# ESP_BLE.net
KiCad netlist of a schematic drawn in Altium Designer
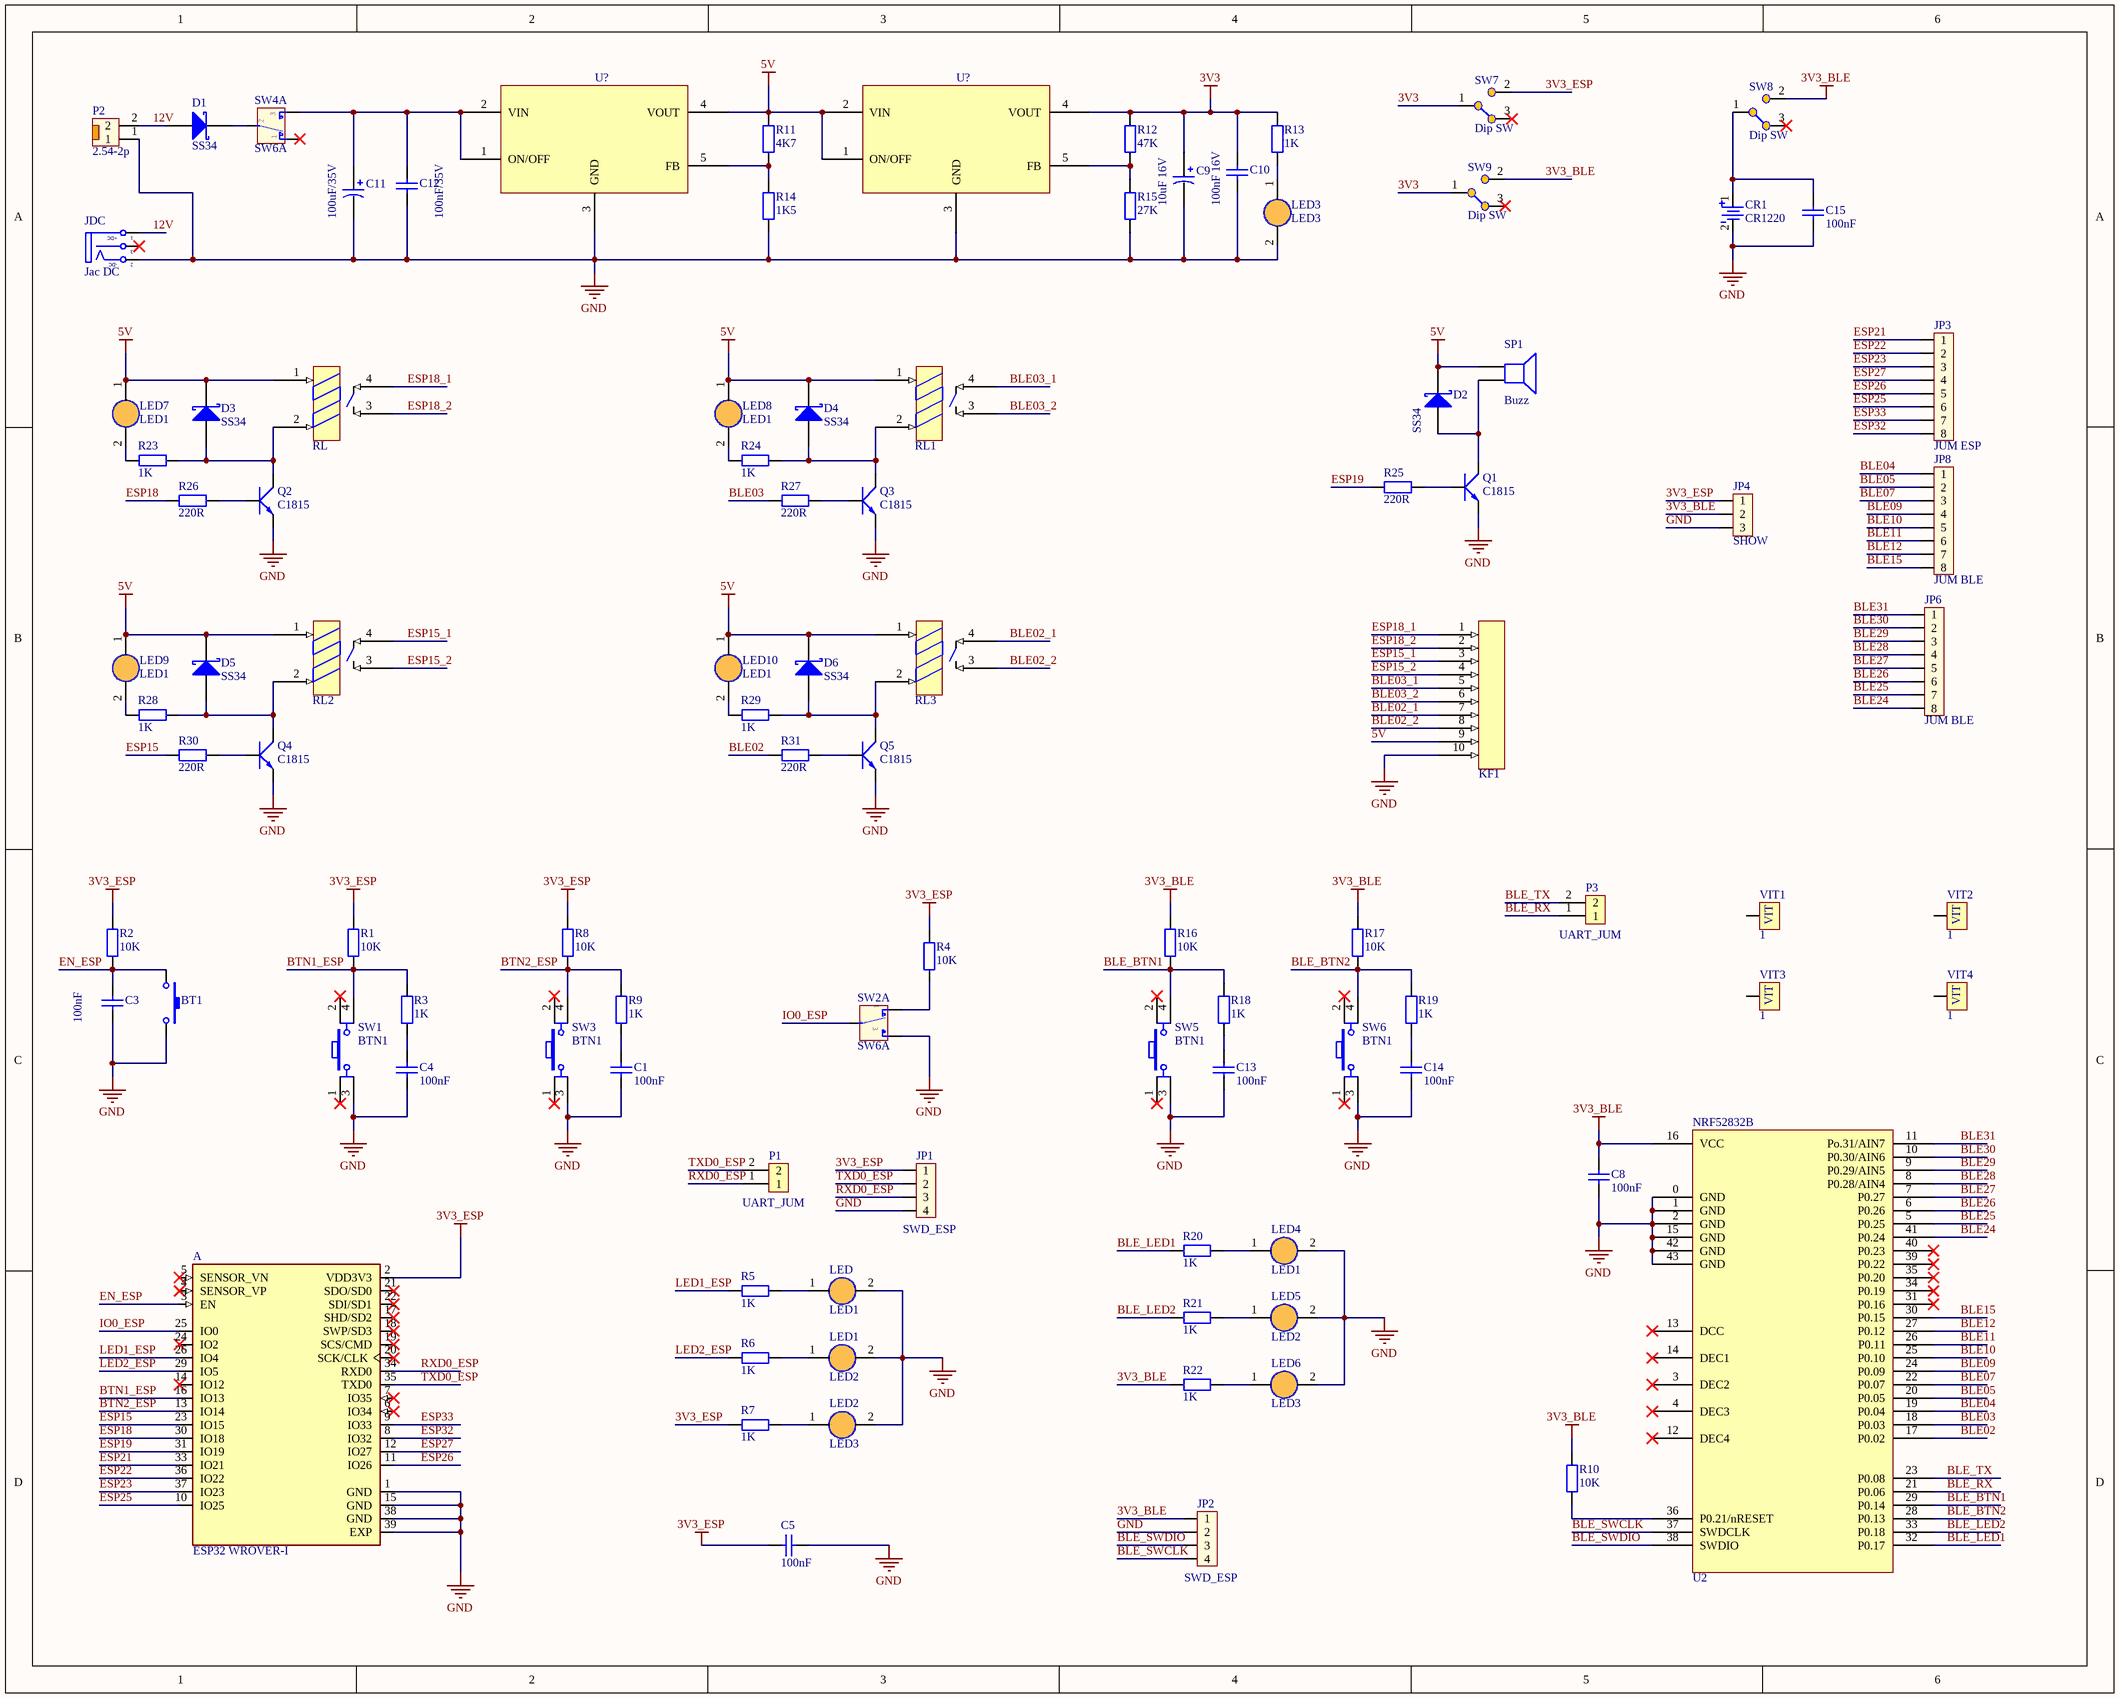
[diagram p0: ESP_BLE.SchDoc]

(export (version "E")
  (design (tool "Eeschema 10.0.6"))
  (components
    (comp (ref "A")
      (value "ESP32 WROVER-I")
      (footprint "ESP32-WROVER-I")
      (fields (field (name "MP") "ESP32-WROVER-I") (field (name "MF") "Espressif Systems"))
      (libsource (lib "Altium_Lib_by_KhueNguyenCreator") (part "ESP32 WROVER-I"))
    )
    (comp (ref "BT1")
      (value "Nút Nhấn 2 Chân 3x6x2.5MM SMD")
      (footprint "Nut Nhan 2 Chan SMD_N")
      (description "Dán")
      (libsource (lib "NhomLib") (part "Nut Nhan 2 Chan SMD"))
    )
    (comp (ref "C1")
      (value "100nF")
      (footprint "tu 0805")
      (description "Dán")
      (libsource (lib "NhomLib") (part "Tu 0805 33nF 50V 20%"))
    )
    (comp (ref "C3")
      (value "100nF")
      (footprint "tu 0805")
      (description "Dán")
      (libsource (lib "NhomLib") (part "Tu 0805 33nF 50V 20%"))
    )
    (comp (ref "C4")
      (value "100nF")
      (footprint "tu 0805")
      (description "Dán")
      (libsource (lib "NhomLib") (part "Tu 0805 33nF 50V 20%"))
    )
    (comp (ref "C5")
      (value "100nF")
      (footprint "tu 0805")
      (description "Dán")
      (libsource (lib "NhomLib") (part "Tu 0805 33nF 50V 20%"))
    )
    (comp (ref "C8")
      (value "100nF")
      (footprint "tu 0805")
      (description "Dán")
      (libsource (lib "NhomLib") (part "Tu 0805 33nF 50V 20%"))
    )
    (comp (ref "C9")
      (value "10uF 16V")
      (footprint "CAP_ALUM_SMD_5054_TYPE_C")
      (description "CAP ALUM 33uF 20% 16V SMD")
      (fields (field (name "MPN") "EEE-FK1C330P") (field (name "MFR") "Panasonic"))
      (libsource (lib "NhomLib") (part "EEE-FK1C330P"))
    )
    (comp (ref "C10")
      (value "100nF 16V")
      (footprint "tu 0805")
      (description "Dán")
      (libsource (lib "NhomLib") (part "Tu 0805 33nF 50V 20%"))
    )
    (comp (ref "C11")
      (value "100uF/35V")
      (footprint "CAP_ALUM_SMD_100102_TYPE_G")
      (description "CAP ALUM 330uF 20% 35V SMD")
      (fields (field (name "MPN") "EEE-FK1C331P") (field (name "MFR") "Panasonic"))
      (libsource (lib "NhomLib") (part "EEE-FK1C331P"))
    )
    (comp (ref "C12")
      (value "100nF/35V")
      (footprint "tu 0805")
      (description "Dán")
      (libsource (lib "NhomLib") (part "Tu 0805 33nF 50V 20%"))
    )
    (comp (ref "C13")
      (value "100nF")
      (footprint "tu 0805")
      (description "Dán")
      (libsource (lib "NhomLib") (part "Tu 0805 33nF 50V 20%"))
    )
    (comp (ref "C14")
      (value "100nF")
      (footprint "tu 0805")
      (description "Dán")
      (libsource (lib "NhomLib") (part "Tu 0805 33nF 50V 20%"))
    )
    (comp (ref "C15")
      (value "100nF")
      (footprint "tu 0805")
      (description "Dán")
      (libsource (lib "NhomLib") (part "Tu 0805 33nF 50V 20%"))
    )
    (comp (ref "CR1")
      (value "CR1220")
      (footprint "CR1220_HOLDER_SMD")
      (libsource (lib "VINH TRI") (part "CR1220"))
    )
    (comp (ref "D1")
      (value "SS34")
      (footprint "DIODE_DO214AC_SMA")
      (description "DIODE SCHOTTKY 40V 3A SMA")
      (libsource (lib "NhomLib") (part "SS34"))
    )
    (comp (ref "D2")
      (value "SS34")
      (footprint "DIODE_DO214AC_SMA")
      (description "DIODE SCHOTTKY 40V 3A SMA")
      (libsource (lib "NhomLib") (part "SS34"))
    )
    (comp (ref "D3")
      (value "SS34")
      (footprint "DIODE_DO214AC_SMA")
      (description "DIODE SCHOTTKY 40V 3A SMA")
      (libsource (lib "NhomLib") (part "SS34"))
    )
    (comp (ref "D4")
      (value "SS34")
      (footprint "DIODE_DO214AC_SMA")
      (description "DIODE SCHOTTKY 40V 3A SMA")
      (libsource (lib "NhomLib") (part "SS34"))
    )
    (comp (ref "D5")
      (value "SS34")
      (footprint "DIODE_DO214AC_SMA")
      (description "DIODE SCHOTTKY 40V 3A SMA")
      (libsource (lib "NhomLib") (part "SS34"))
    )
    (comp (ref "D6")
      (value "SS34")
      (footprint "DIODE_DO214AC_SMA")
      (description "DIODE SCHOTTKY 40V 3A SMA")
      (libsource (lib "NhomLib") (part "SS34"))
    )
    (comp (ref "JDC")
      (value "Jac DC")
      (footprint "DC-IN")
      (description "Jac DC input")
      (libsource (lib "NhomLib") (part "DCIN"))
    )
    (comp (ref "JP1")
      (value "SWD_ESP")
      (footprint "JUMP DON DUC 2.54_4P")
      (description "Cắm")
      (libsource (lib "SCH Chuan") (part "Jump Don Duc 2.54_4P"))
    )
    (comp (ref "JP2")
      (value "SWD_ESP")
      (footprint "JUMP DON DUC 2.54_4P")
      (description "Cắm")
      (libsource (lib "SCH Chuan") (part "Jump Don Duc 2.54_4P"))
    )
    (comp (ref "JP3")
      (value "JUM ESP")
      (footprint "Jump Don Duc Thang 2.54_8p")
      (description "Cắm")
      (libsource (lib "NhomLib") (part "Jump Don Duc 2.54_8P"))
    )
    (comp (ref "JP4")
      (value "SHOW")
      (footprint "jump don duc thang 2.54_3p")
      (description "Cắm")
      (libsource (lib "NhomLib") (part "Jump Don Duc 2.54_3P"))
    )
    (comp (ref "JP6")
      (value "JUM BLE")
      (footprint "Jump Don Duc Thang 2.54_8p")
      (description "Cắm")
      (libsource (lib "NhomLib") (part "Jump Don Duc 2.54_8P"))
    )
    (comp (ref "JP8")
      (value "JUM BLE")
      (footprint "Jump Don Duc Thang 2.54_8p")
      (description "Cắm")
      (libsource (lib "NhomLib") (part "Jump Don Duc 2.54_8P"))
    )
    (comp (ref "KF1")
      (value "KF142R-10")
      (footprint "KF10")
      (description "KF142R-10P-5.08mm")
      (libsource (lib "B212H_01") (part "KF10"))
    )
    (comp (ref "LED")
      (value "LED1")
      (footprint "led 0805")
      (description "Dán")
      (libsource (lib "NhomLib") (part "Led 0805 Xanh Duong"))
    )
    (comp (ref "LED1")
      (value "LED2")
      (footprint "led 0805")
      (description "Dán")
      (libsource (lib "NhomLib") (part "Led 0805 Xanh Duong"))
    )
    (comp (ref "LED2")
      (value "LED3")
      (footprint "led 0805")
      (description "Dán")
      (libsource (lib "NhomLib") (part "Led 0805 Xanh Duong"))
    )
    (comp (ref "LED3")
      (value "LED3")
      (footprint "led 0805")
      (description "Dán")
      (libsource (lib "NhomLib") (part "Led 0805 Xanh Duong"))
    )
    (comp (ref "LED4")
      (value "LED1")
      (footprint "led 0805")
      (description "Dán")
      (libsource (lib "NhomLib") (part "Led 0805 Xanh Duong"))
    )
    (comp (ref "LED5")
      (value "LED2")
      (footprint "led 0805")
      (description "Dán")
      (libsource (lib "NhomLib") (part "Led 0805 Xanh Duong"))
    )
    (comp (ref "LED6")
      (value "LED3")
      (footprint "led 0805")
      (description "Dán")
      (libsource (lib "NhomLib") (part "Led 0805 Xanh Duong"))
    )
    (comp (ref "LED7")
      (value "LED1")
      (footprint "led 0805")
      (description "Dán")
      (libsource (lib "NhomLib") (part "Led 0805 Xanh Duong"))
    )
    (comp (ref "LED8")
      (value "LED1")
      (footprint "led 0805")
      (description "Dán")
      (libsource (lib "NhomLib") (part "Led 0805 Xanh Duong"))
    )
    (comp (ref "LED9")
      (value "LED1")
      (footprint "led 0805")
      (description "Dán")
      (libsource (lib "NhomLib") (part "Led 0805 Xanh Duong"))
    )
    (comp (ref "LED10")
      (value "LED1")
      (footprint "led 0805")
      (description "Dán")
      (libsource (lib "NhomLib") (part "Led 0805 Xanh Duong"))
    )
    (comp (ref "MIC1")
      (value "U?")
      (footprint "Mic5V")
      (description "3A")
      (libsource (lib "node_mcu") (part "Mic5V"))
    )
    (comp (ref "MIC2")
      (value "U?")
      (footprint "Mic5V")
      (description "3A")
      (libsource (lib "node_mcu") (part "Mic5V"))
    )
    (comp (ref "NRF52832") (value "U2") (footprint "NRF52832") (libsource (lib "NRF52832") (part "U?")))
    (comp (ref "P1")
      (value "UART_JUM")
      (footprint "Jump don duc 2.54_2P")
      (description "Cắm")
      (libsource (lib "NhomLib") (part "jump don duc 2.54_2p"))
    )
    (comp (ref "P2")
      (value "2.54-2p")
      (footprint "Header Duc Thang 2P 2.54")
      (description "Cắm")
      (libsource (lib "NhomLib") (part "Header 2.54-2p Duc Thang"))
    )
    (comp (ref "P3")
      (value "UART_JUM")
      (footprint "Jump don duc 2.54_2P")
      (description "Cắm")
      (libsource (lib "NhomLib") (part "jump don duc 2.54_2p"))
    )
    (comp (ref "Q1")
      (value "C1815")
      (footprint "SOT23B")
      (description "NPN 600mW, ECB")
      (libsource (lib "syhaunguyen") (part "C1815"))
    )
    (comp (ref "Q2")
      (value "C1815")
      (footprint "SOT23B")
      (description "NPN 600mW, ECB")
      (libsource (lib "syhaunguyen") (part "C1815"))
    )
    (comp (ref "Q3")
      (value "C1815")
      (footprint "SOT23B")
      (description "NPN 600mW, ECB")
      (libsource (lib "syhaunguyen") (part "C1815"))
    )
    (comp (ref "Q4")
      (value "C1815")
      (footprint "SOT23B")
      (description "NPN 600mW, ECB")
      (libsource (lib "syhaunguyen") (part "C1815"))
    )
    (comp (ref "Q5")
      (value "C1815")
      (footprint "SOT23B")
      (description "NPN 600mW, ECB")
      (libsource (lib "syhaunguyen") (part "C1815"))
    )
    (comp (ref "R1")
      (value "10K")
      (footprint "tro 0805")
      (description "Dán")
      (libsource (lib "NhomLib") (part "Tro 0805 1% 0.33R"))
    )
    (comp (ref "R2")
      (value "10K")
      (footprint "tro 0805")
      (description "Dán")
      (libsource (lib "NhomLib") (part "Tro 0805 1% 0.33R"))
    )
    (comp (ref "R3")
      (value "1K")
      (footprint "tro 0805")
      (description "Dán")
      (libsource (lib "NhomLib") (part "Tro 0805 1% 0.33R"))
    )
    (comp (ref "R4")
      (value "10K")
      (footprint "tro 0805")
      (description "Dán")
      (libsource (lib "NhomLib") (part "Tro 0805 1% 0.33R"))
    )
    (comp (ref "R5")
      (value "1K")
      (footprint "tro 0805")
      (description "Dán")
      (libsource (lib "NhomLib") (part "Tro 0805 1% 0.33R"))
    )
    (comp (ref "R6")
      (value "1K")
      (footprint "tro 0805")
      (description "Dán")
      (libsource (lib "NhomLib") (part "Tro 0805 1% 0.33R"))
    )
    (comp (ref "R7")
      (value "1K")
      (footprint "tro 0805")
      (description "Dán")
      (libsource (lib "NhomLib") (part "Tro 0805 1% 0.33R"))
    )
    (comp (ref "R8")
      (value "10K")
      (footprint "tro 0805")
      (description "Dán")
      (libsource (lib "NhomLib") (part "Tro 0805 1% 0.33R"))
    )
    (comp (ref "R9")
      (value "1K")
      (footprint "tro 0805")
      (description "Dán")
      (libsource (lib "NhomLib") (part "Tro 0805 1% 0.33R"))
    )
    (comp (ref "R10")
      (value "10K")
      (footprint "tro 0805")
      (description "Dán")
      (libsource (lib "NhomLib") (part "Tro 0805 1% 0.33R"))
    )
    (comp (ref "R11")
      (value "4K7")
      (footprint "tro 0805")
      (description "Dán")
      (libsource (lib "NhomLib") (part "Tro 0805 1% 0.33R"))
    )
    (comp (ref "R12")
      (value "47K")
      (footprint "tro 0805")
      (description "Dán")
      (libsource (lib "NhomLib") (part "Tro 0805 1% 0.33R"))
    )
    (comp (ref "R13")
      (value "1K")
      (footprint "tro 0805")
      (description "Dán")
      (libsource (lib "NhomLib") (part "Tro 0805 1% 0.33R"))
    )
    (comp (ref "R14")
      (value "1K5")
      (footprint "tro 0805")
      (description "Dán")
      (libsource (lib "NhomLib") (part "Tro 0805 1% 0.33R"))
    )
    (comp (ref "R15")
      (value "27K")
      (footprint "tro 0805")
      (description "Dán")
      (libsource (lib "NhomLib") (part "Tro 0805 1% 0.33R"))
    )
    (comp (ref "R16")
      (value "10K")
      (footprint "tro 0805")
      (description "Dán")
      (libsource (lib "NhomLib") (part "Tro 0805 1% 0.33R"))
    )
    (comp (ref "R17")
      (value "10K")
      (footprint "tro 0805")
      (description "Dán")
      (libsource (lib "NhomLib") (part "Tro 0805 1% 0.33R"))
    )
    (comp (ref "R18")
      (value "1K")
      (footprint "tro 0805")
      (description "Dán")
      (libsource (lib "NhomLib") (part "Tro 0805 1% 0.33R"))
    )
    (comp (ref "R19")
      (value "1K")
      (footprint "tro 0805")
      (description "Dán")
      (libsource (lib "NhomLib") (part "Tro 0805 1% 0.33R"))
    )
    (comp (ref "R20")
      (value "1K")
      (footprint "tro 0805")
      (description "Dán")
      (libsource (lib "NhomLib") (part "Tro 0805 1% 0.33R"))
    )
    (comp (ref "R21")
      (value "1K")
      (footprint "tro 0805")
      (description "Dán")
      (libsource (lib "NhomLib") (part "Tro 0805 1% 0.33R"))
    )
    (comp (ref "R22")
      (value "1K")
      (footprint "tro 0805")
      (description "Dán")
      (libsource (lib "NhomLib") (part "Tro 0805 1% 0.33R"))
    )
    (comp (ref "R23")
      (value "1K")
      (footprint "tro 0805")
      (description "Dán")
      (libsource (lib "NhomLib") (part "Tro 0805 1% 0.33R"))
    )
    (comp (ref "R24")
      (value "1K")
      (footprint "tro 0805")
      (description "Dán")
      (libsource (lib "NhomLib") (part "Tro 0805 1% 0.33R"))
    )
    (comp (ref "R25")
      (value "220R")
      (footprint "tro 0805")
      (description "Dán")
      (libsource (lib "NhomLib") (part "Tro 0805 1% 0.33R"))
    )
    (comp (ref "R26")
      (value "220R")
      (footprint "tro 0805")
      (description "Dán")
      (libsource (lib "NhomLib") (part "Tro 0805 1% 0.33R"))
    )
    (comp (ref "R27")
      (value "220R")
      (footprint "tro 0805")
      (description "Dán")
      (libsource (lib "NhomLib") (part "Tro 0805 1% 0.33R"))
    )
    (comp (ref "R28")
      (value "1K")
      (footprint "tro 0805")
      (description "Dán")
      (libsource (lib "NhomLib") (part "Tro 0805 1% 0.33R"))
    )
    (comp (ref "R29")
      (value "1K")
      (footprint "tro 0805")
      (description "Dán")
      (libsource (lib "NhomLib") (part "Tro 0805 1% 0.33R"))
    )
    (comp (ref "R30")
      (value "220R")
      (footprint "tro 0805")
      (description "Dán")
      (libsource (lib "NhomLib") (part "Tro 0805 1% 0.33R"))
    )
    (comp (ref "R31")
      (value "220R")
      (footprint "tro 0805")
      (description "Dán")
      (libsource (lib "NhomLib") (part "Tro 0805 1% 0.33R"))
    )
    (comp (ref "RL") (value "Relay-4") (footprint "Relay-4") (libsource (lib "B212H_01") (part "Relay-4")))
    (comp (ref "RL1") (value "Relay-4") (footprint "Relay-4") (libsource (lib "B212H_01") (part "Relay-4")))
    (comp (ref "RL2") (value "Relay-4") (footprint "Relay-4") (libsource (lib "B212H_01") (part "Relay-4")))
    (comp (ref "RL3") (value "Relay-4") (footprint "Relay-4") (libsource (lib "B212H_01") (part "Relay-4")))
    (comp (ref "SP1")
      (value "Buzz")
      (footprint "SPEAKER")
      (description "Cắm")
      (libsource (lib "SCH Chuan") (part "Coi Chip 5V"))
    )
    (comp (ref "SW1")
      (value "BTN1")
      (footprint "SW-4P-S")
      (description "Cắm")
      (libsource (lib "NhomLib") (part "Nut Nhan 4 Chan"))
    )
    (comp (ref "SW2")
      (value "SW6A")
      (footprint "SW6")
      (description "SW-DTDP - 6 Pin")
      (libsource (lib "") (part "SW6A_1"))
    )
    (comp (ref "SW3")
      (value "BTN1")
      (footprint "SW-4P-S")
      (description "Cắm")
      (libsource (lib "NhomLib") (part "Nut Nhan 4 Chan"))
    )
    (comp (ref "SW4")
      (value "SW6A")
      (footprint "SW6")
      (description "SW-DTDP - 6 Pin")
      (libsource (lib "NhomLib") (part "SW6A"))
    )
    (comp (ref "SW5")
      (value "BTN1")
      (footprint "SW-4P-S")
      (description "Cắm")
      (libsource (lib "NhomLib") (part "Nut Nhan 4 Chan"))
    )
    (comp (ref "SW6")
      (value "BTN1")
      (footprint "SW-4P-S")
      (description "Cắm")
      (libsource (lib "NhomLib") (part "Nut Nhan 4 Chan"))
    )
    (comp (ref "SW7")
      (value "Dip SW")
      (footprint "SW3P")
      (description "Dip Switch 3 pin")
      (libsource (lib "VPMyLibrary") (part "Switch3P"))
    )
    (comp (ref "SW8")
      (value "Dip SW")
      (footprint "SW3P")
      (description "Dip Switch 3 pin")
      (libsource (lib "VPMyLibrary") (part "Switch3P"))
    )
    (comp (ref "SW9")
      (value "Dip SW")
      (footprint "SW3P")
      (description "Dip Switch 3 pin")
      (libsource (lib "VPMyLibrary") (part "Switch3P"))
    )
    (comp (ref "VIT1")
      (value "1")
      (footprint "VIT")
      (description "Oc Vit")
      (libsource (lib "NhomLib") (part "VIT"))
    )
    (comp (ref "VIT2")
      (value "1")
      (footprint "VIT")
      (description "Oc Vit")
      (libsource (lib "NhomLib") (part "VIT"))
    )
    (comp (ref "VIT3")
      (value "1")
      (footprint "VIT")
      (description "Oc Vit")
      (libsource (lib "NhomLib") (part "VIT"))
    )
    (comp (ref "VIT4")
      (value "1")
      (footprint "VIT")
      (description "Oc Vit")
      (libsource (lib "NhomLib") (part "VIT"))
    )
  )
  (nets
    (net (code "1") (name "/12V") (class "Default")
      (node (ref "D1") (pin "1") (pinfunction "A_1") (pintype "passive"))
      (node (ref "JDC") (pin "1") (pinfunction "T_1") (pintype "passive"))
      (node (ref "P2") (pin "2") (pinfunction "2_2") (pintype "passive"))
    )
    (net (code "2") (name "/BLE02") (class "Default")
      (node (ref "NRF52832") (pin "17") (pinfunction "P0.02_17") (pintype "passive"))
      (node (ref "R31") (pin "2") (pinfunction "2_2") (pintype "passive"))
    )
    (net (code "3") (name "/BLE02_1") (class "Default")
      (node (ref "KF1") (pin "7") (pintype "input"))
      (node (ref "RL3") (pin "4") (pintype "input"))
    )
    (net (code "4") (name "/BLE02_2") (class "Default")
      (node (ref "KF1") (pin "8") (pintype "input"))
      (node (ref "RL3") (pin "3") (pintype "input"))
    )
    (net (code "5") (name "/BLE03") (class "Default")
      (node (ref "NRF52832") (pin "18") (pinfunction "P0.03_18") (pintype "passive"))
      (node (ref "R27") (pin "2") (pinfunction "2_2") (pintype "passive"))
    )
    (net (code "6") (name "/BLE03_1") (class "Default")
      (node (ref "KF1") (pin "5") (pintype "input"))
      (node (ref "RL1") (pin "4") (pintype "input"))
    )
    (net (code "7") (name "/BLE03_2") (class "Default")
      (node (ref "KF1") (pin "6") (pintype "input"))
      (node (ref "RL1") (pin "3") (pintype "input"))
    )
    (net (code "8") (name "/BLE04") (class "Default")
      (node (ref "JP8") (pin "1") (pinfunction "1_1") (pintype "passive"))
      (node (ref "NRF52832") (pin "19") (pinfunction "P0.04_19") (pintype "passive"))
    )
    (net (code "9") (name "/BLE05") (class "Default")
      (node (ref "JP8") (pin "2") (pinfunction "2_2") (pintype "passive"))
      (node (ref "NRF52832") (pin "20") (pinfunction "P0.05_20") (pintype "passive"))
    )
    (net (code "10") (name "/BLE07") (class "Default")
      (node (ref "JP8") (pin "3") (pinfunction "3_3") (pintype "passive"))
      (node (ref "NRF52832") (pin "22") (pinfunction "P0.07_22") (pintype "passive"))
    )
    (net (code "11") (name "/BLE09") (class "Default")
      (node (ref "JP8") (pin "4") (pinfunction "4_4") (pintype "passive"))
      (node (ref "NRF52832") (pin "24") (pinfunction "P0.09_24") (pintype "passive"))
    )
    (net (code "12") (name "/BLE10") (class "Default")
      (node (ref "JP8") (pin "5") (pinfunction "5_5") (pintype "passive"))
      (node (ref "NRF52832") (pin "25") (pinfunction "P0.10_25") (pintype "passive"))
    )
    (net (code "13") (name "/BLE11") (class "Default")
      (node (ref "JP8") (pin "6") (pinfunction "6_6") (pintype "passive"))
      (node (ref "NRF52832") (pin "26") (pinfunction "P0.11_26") (pintype "passive"))
    )
    (net (code "14") (name "/BLE12") (class "Default")
      (node (ref "JP8") (pin "7") (pinfunction "7_7") (pintype "passive"))
      (node (ref "NRF52832") (pin "27") (pinfunction "P0.12_27") (pintype "passive"))
    )
    (net (code "15") (name "/BLE15") (class "Default")
      (node (ref "JP8") (pin "8") (pinfunction "8_8") (pintype "passive"))
      (node (ref "NRF52832") (pin "30") (pinfunction "P0.15_30") (pintype "passive"))
    )
    (net (code "16") (name "/BLE24") (class "Default")
      (node (ref "JP6") (pin "8") (pinfunction "8_8") (pintype "passive"))
      (node (ref "NRF52832") (pin "41") (pinfunction "P0.24_41") (pintype "passive"))
    )
    (net (code "17") (name "/BLE25") (class "Default")
      (node (ref "JP6") (pin "7") (pinfunction "7_7") (pintype "passive"))
      (node (ref "NRF52832") (pin "5") (pinfunction "P0.25_5") (pintype "passive"))
    )
    (net (code "18") (name "/BLE26") (class "Default")
      (node (ref "JP6") (pin "6") (pinfunction "6_6") (pintype "passive"))
      (node (ref "NRF52832") (pin "6") (pinfunction "P0.26_6") (pintype "passive"))
    )
    (net (code "19") (name "/BLE27") (class "Default")
      (node (ref "JP6") (pin "5") (pinfunction "5_5") (pintype "passive"))
      (node (ref "NRF52832") (pin "7") (pinfunction "P0.27_7") (pintype "passive"))
    )
    (net (code "20") (name "/BLE28") (class "Default")
      (node (ref "JP6") (pin "4") (pinfunction "4_4") (pintype "passive"))
      (node (ref "NRF52832") (pin "8") (pinfunction "P0.28/AIN4_8") (pintype "passive"))
    )
    (net (code "21") (name "/BLE29") (class "Default")
      (node (ref "JP6") (pin "3") (pinfunction "3_3") (pintype "passive"))
      (node (ref "NRF52832") (pin "9") (pinfunction "P0.29/AIN5_9") (pintype "passive"))
    )
    (net (code "22") (name "/BLE30") (class "Default")
      (node (ref "JP6") (pin "2") (pinfunction "2_2") (pintype "passive"))
      (node (ref "NRF52832") (pin "10") (pinfunction "P0.30/AIN6_10") (pintype "passive"))
    )
    (net (code "23") (name "/BLE31") (class "Default")
      (node (ref "JP6") (pin "1") (pinfunction "1_1") (pintype "passive"))
      (node (ref "NRF52832") (pin "11") (pinfunction "Po.31/AIN7_11") (pintype "passive"))
    )
    (net (code "24") (name "/BLE_BTN1") (class "Default")
      (node (ref "NRF52832") (pin "29") (pinfunction "P0.14_29") (pintype "passive"))
      (node (ref "R16") (pin "1") (pinfunction "1_1") (pintype "passive"))
      (node (ref "R18") (pin "1") (pinfunction "1_1") (pintype "passive"))
      (node (ref "SW5") (pin "4") (pintype "passive"))
    )
    (net (code "25") (name "/BLE_BTN2") (class "Default")
      (node (ref "NRF52832") (pin "28") (pinfunction "P0.13_28") (pintype "passive"))
      (node (ref "R17") (pin "1") (pinfunction "1_1") (pintype "passive"))
      (node (ref "R19") (pin "1") (pinfunction "1_1") (pintype "passive"))
      (node (ref "SW6") (pin "4") (pintype "passive"))
    )
    (net (code "26") (name "/BLE_LED1") (class "Default")
      (node (ref "NRF52832") (pin "32") (pinfunction "P0.17_32") (pintype "passive"))
      (node (ref "R20") (pin "1") (pinfunction "1_1") (pintype "passive"))
    )
    (net (code "27") (name "/BLE_LED2") (class "Default")
      (node (ref "NRF52832") (pin "33") (pinfunction "P0.18_33") (pintype "passive"))
      (node (ref "R21") (pin "1") (pinfunction "1_1") (pintype "passive"))
    )
    (net (code "28") (name "/BLE_RX") (class "Default")
      (node (ref "NRF52832") (pin "21") (pinfunction "P0.06_21") (pintype "passive"))
      (node (ref "P3") (pin "1") (pinfunction "1_1") (pintype "passive"))
    )
    (net (code "29") (name "/BLE_SWCLK") (class "Default")
      (node (ref "JP2") (pin "4") (pinfunction "4_4") (pintype "passive"))
      (node (ref "NRF52832") (pin "37") (pinfunction "SWDCLK_37") (pintype "passive"))
    )
    (net (code "30") (name "/BLE_SWDIO") (class "Default")
      (node (ref "JP2") (pin "3") (pinfunction "3_3") (pintype "passive"))
      (node (ref "NRF52832") (pin "38") (pinfunction "SWDIO_38") (pintype "passive"))
    )
    (net (code "31") (name "/BLE_TX") (class "Default")
      (node (ref "NRF52832") (pin "23") (pinfunction "P0.08_23") (pintype "passive"))
      (node (ref "P3") (pin "2") (pinfunction "2_2") (pintype "passive"))
    )
    (net (code "32") (name "/BTN1_ESP") (class "Default")
      (node (ref "A") (pin "16") (pinfunction "IO13_16") (pintype "bidirectional"))
      (node (ref "R1") (pin "1") (pinfunction "1_1") (pintype "passive"))
      (node (ref "R3") (pin "1") (pinfunction "1_1") (pintype "passive"))
      (node (ref "SW1") (pin "4") (pintype "passive"))
    )
    (net (code "33") (name "/BTN2_ESP") (class "Default")
      (node (ref "A") (pin "13") (pinfunction "IO14_13") (pintype "bidirectional"))
      (node (ref "R8") (pin "1") (pinfunction "1_1") (pintype "passive"))
      (node (ref "R9") (pin "1") (pinfunction "1_1") (pintype "passive"))
      (node (ref "SW3") (pin "4") (pintype "passive"))
    )
    (net (code "34") (name "/EN_ESP") (class "Default")
      (node (ref "A") (pin "3") (pinfunction "EN_3") (pintype "input"))
      (node (ref "BT1") (pin "1") (pinfunction "1_1") (pintype "passive"))
      (node (ref "C3") (pin "1") (pinfunction "1_1") (pintype "passive"))
      (node (ref "R2") (pin "1") (pinfunction "1_1") (pintype "passive"))
    )
    (net (code "35") (name "/ESP15") (class "Default")
      (node (ref "A") (pin "23") (pinfunction "IO15_23") (pintype "bidirectional"))
      (node (ref "R30") (pin "2") (pinfunction "2_2") (pintype "passive"))
    )
    (net (code "36") (name "/ESP15_1") (class "Default")
      (node (ref "KF1") (pin "3") (pintype "input"))
      (node (ref "RL2") (pin "4") (pintype "input"))
    )
    (net (code "37") (name "/ESP15_2") (class "Default")
      (node (ref "KF1") (pin "4") (pintype "input"))
      (node (ref "RL2") (pin "3") (pintype "input"))
    )
    (net (code "38") (name "/ESP18") (class "Default")
      (node (ref "A") (pin "30") (pinfunction "IO18_30") (pintype "bidirectional"))
      (node (ref "R26") (pin "2") (pinfunction "2_2") (pintype "passive"))
    )
    (net (code "39") (name "/ESP18_1") (class "Default")
      (node (ref "KF1") (pin "1") (pintype "input"))
      (node (ref "RL") (pin "4") (pintype "input"))
    )
    (net (code "40") (name "/ESP18_2") (class "Default")
      (node (ref "KF1") (pin "2") (pintype "input"))
      (node (ref "RL") (pin "3") (pintype "input"))
    )
    (net (code "41") (name "/ESP19") (class "Default")
      (node (ref "A") (pin "31") (pinfunction "IO19_31") (pintype "bidirectional"))
      (node (ref "R25") (pin "2") (pinfunction "2_2") (pintype "passive"))
    )
    (net (code "42") (name "/ESP21") (class "Default")
      (node (ref "A") (pin "33") (pinfunction "IO21_33") (pintype "bidirectional"))
      (node (ref "JP3") (pin "1") (pinfunction "1_1") (pintype "passive"))
    )
    (net (code "43") (name "/ESP22") (class "Default")
      (node (ref "A") (pin "36") (pinfunction "IO22_36") (pintype "bidirectional"))
      (node (ref "JP3") (pin "2") (pinfunction "2_2") (pintype "passive"))
    )
    (net (code "44") (name "/ESP23") (class "Default")
      (node (ref "A") (pin "37") (pinfunction "IO23_37") (pintype "bidirectional"))
      (node (ref "JP3") (pin "3") (pinfunction "3_3") (pintype "passive"))
    )
    (net (code "45") (name "/ESP25") (class "Default")
      (node (ref "A") (pin "10") (pinfunction "IO25_10") (pintype "bidirectional"))
      (node (ref "JP3") (pin "6") (pinfunction "6_6") (pintype "passive"))
    )
    (net (code "46") (name "/ESP26") (class "Default")
      (node (ref "A") (pin "11") (pinfunction "IO26_11") (pintype "bidirectional"))
      (node (ref "JP3") (pin "5") (pinfunction "5_5") (pintype "passive"))
    )
    (net (code "47") (name "/ESP27") (class "Default")
      (node (ref "A") (pin "12") (pinfunction "IO27_12") (pintype "bidirectional"))
      (node (ref "JP3") (pin "4") (pinfunction "4_4") (pintype "passive"))
    )
    (net (code "48") (name "/ESP32") (class "Default")
      (node (ref "A") (pin "8") (pinfunction "IO32_8") (pintype "bidirectional"))
      (node (ref "JP3") (pin "8") (pinfunction "8_8") (pintype "passive"))
    )
    (net (code "49") (name "/ESP33") (class "Default")
      (node (ref "A") (pin "9") (pinfunction "IO33_9") (pintype "bidirectional"))
      (node (ref "JP3") (pin "7") (pinfunction "7_7") (pintype "passive"))
    )
    (net (code "50") (name "/IO0_ESP") (class "Default")
      (node (ref "A") (pin "25") (pinfunction "IO0_25") (pintype "bidirectional"))
      (node (ref "SW2") (pin "2") (pinfunction "2_2") (pintype "passive"))
    )
    (net (code "51") (name "/LED1_ESP") (class "Default")
      (node (ref "A") (pin "26") (pinfunction "IO4_26") (pintype "bidirectional"))
      (node (ref "R5") (pin "1") (pinfunction "1_1") (pintype "passive"))
    )
    (net (code "52") (name "/LED2_ESP") (class "Default")
      (node (ref "A") (pin "29") (pinfunction "IO5_29") (pintype "bidirectional"))
      (node (ref "R6") (pin "1") (pinfunction "1_1") (pintype "passive"))
    )
    (net (code "53") (name "/RXD0_ESP") (class "Default")
      (node (ref "A") (pin "34") (pinfunction "RXD0_34") (pintype "bidirectional"))
      (node (ref "JP1") (pin "3") (pinfunction "3_3") (pintype "passive"))
      (node (ref "P1") (pin "1") (pinfunction "1_1") (pintype "passive"))
    )
    (net (code "54") (name "/TXD0_ESP") (class "Default")
      (node (ref "A") (pin "35") (pinfunction "TXD0_35") (pintype "bidirectional"))
      (node (ref "JP1") (pin "2") (pinfunction "2_2") (pintype "passive"))
      (node (ref "P1") (pin "2") (pinfunction "2_2") (pintype "passive"))
    )
    (net (code "55") (name "3V3") (class "Default")
      (node (ref "C10") (pin "1") (pinfunction "1_1") (pintype "passive"))
      (node (ref "C9") (pin "1") (pinfunction "1_1") (pintype "passive"))
      (node (ref "MIC2") (pin "4") (pinfunction "VOUT_4") (pintype "passive"))
      (node (ref "R12") (pin "2") (pinfunction "2_2") (pintype "passive"))
      (node (ref "R13") (pin "2") (pinfunction "2_2") (pintype "passive"))
      (node (ref "SW7") (pin "1") (pinfunction "COM_1") (pintype "passive"))
      (node (ref "SW9") (pin "1") (pinfunction "COM_1") (pintype "passive"))
    )
    (net (code "56") (name "3V3_BLE") (class "Default")
      (node (ref "C8") (pin "1") (pinfunction "1_1") (pintype "passive"))
      (node (ref "JP2") (pin "1") (pinfunction "1_1") (pintype "passive"))
      (node (ref "JP4") (pin "2") (pinfunction "2_2") (pintype "passive"))
      (node (ref "NRF52832") (pin "16") (pinfunction "VCC_16") (pintype "passive"))
      (node (ref "R10") (pin "2") (pinfunction "2_2") (pintype "passive"))
      (node (ref "R16") (pin "2") (pinfunction "2_2") (pintype "passive"))
      (node (ref "R17") (pin "2") (pinfunction "2_2") (pintype "passive"))
      (node (ref "R22") (pin "1") (pinfunction "1_1") (pintype "passive"))
      (node (ref "SW8") (pin "2") (pinfunction "NC_2") (pintype "passive"))
      (node (ref "SW9") (pin "2") (pinfunction "NC_2") (pintype "passive"))
    )
    (net (code "57") (name "3V3_ESP") (class "Default")
      (node (ref "A") (pin "2") (pinfunction "VDD3V3_2") (pintype "power_in"))
      (node (ref "C5") (pin "1") (pinfunction "1_1") (pintype "passive"))
      (node (ref "JP1") (pin "1") (pinfunction "1_1") (pintype "passive"))
      (node (ref "JP4") (pin "1") (pinfunction "1_1") (pintype "passive"))
      (node (ref "R1") (pin "2") (pinfunction "2_2") (pintype "passive"))
      (node (ref "R2") (pin "2") (pinfunction "2_2") (pintype "passive"))
      (node (ref "R4") (pin "2") (pinfunction "2_2") (pintype "passive"))
      (node (ref "R7") (pin "1") (pinfunction "1_1") (pintype "passive"))
      (node (ref "R8") (pin "2") (pinfunction "2_2") (pintype "passive"))
      (node (ref "SW7") (pin "2") (pinfunction "NC_2") (pintype "passive"))
    )
    (net (code "58") (name "5V") (class "Default")
      (node (ref "D2") (pin "2") (pinfunction "K_2") (pintype "passive"))
      (node (ref "D3") (pin "2") (pinfunction "K_2") (pintype "passive"))
      (node (ref "D4") (pin "2") (pinfunction "K_2") (pintype "passive"))
      (node (ref "D5") (pin "2") (pinfunction "K_2") (pintype "passive"))
      (node (ref "D6") (pin "2") (pinfunction "K_2") (pintype "passive"))
      (node (ref "KF1") (pin "9") (pintype "input"))
      (node (ref "LED10") (pin "1") (pinfunction "A_1") (pintype "passive"))
      (node (ref "LED7") (pin "1") (pinfunction "A_1") (pintype "passive"))
      (node (ref "LED8") (pin "1") (pinfunction "A_1") (pintype "passive"))
      (node (ref "LED9") (pin "1") (pinfunction "A_1") (pintype "passive"))
      (node (ref "MIC1") (pin "4") (pinfunction "VOUT_4") (pintype "passive"))
      (node (ref "MIC2") (pin "1") (pinfunction "ON/OFF_1") (pintype "passive"))
      (node (ref "MIC2") (pin "2") (pinfunction "VIN_2") (pintype "passive"))
      (node (ref "R11") (pin "2") (pinfunction "2_2") (pintype "passive"))
      (node (ref "RL") (pin "1") (pintype "input"))
      (node (ref "RL1") (pin "1") (pintype "input"))
      (node (ref "RL2") (pin "1") (pintype "input"))
      (node (ref "RL3") (pin "1") (pintype "input"))
      (node (ref "SP1") (pin "1") (pinfunction "1_1") (pintype "passive"))
    )
    (net (code "59") (name "GND") (class "Default")
      (node (ref "A") (pin "1") (pinfunction "GND_1") (pintype "power_in"))
      (node (ref "A") (pin "15") (pinfunction "GND_15") (pintype "power_in"))
      (node (ref "A") (pin "38") (pinfunction "GND_38") (pintype "power_in"))
      (node (ref "A") (pin "39") (pinfunction "EXP_39") (pintype "power_in"))
      (node (ref "BT1") (pin "2") (pinfunction "2_2") (pintype "passive"))
      (node (ref "C1") (pin "2") (pinfunction "2_2") (pintype "passive"))
      (node (ref "C10") (pin "2") (pinfunction "2_2") (pintype "passive"))
      (node (ref "C11") (pin "2") (pinfunction "2_2") (pintype "passive"))
      (node (ref "C12") (pin "2") (pinfunction "2_2") (pintype "passive"))
      (node (ref "C13") (pin "2") (pinfunction "2_2") (pintype "passive"))
      (node (ref "C14") (pin "2") (pinfunction "2_2") (pintype "passive"))
      (node (ref "C15") (pin "2") (pinfunction "2_2") (pintype "passive"))
      (node (ref "C3") (pin "2") (pinfunction "2_2") (pintype "passive"))
      (node (ref "C4") (pin "2") (pinfunction "2_2") (pintype "passive"))
      (node (ref "C5") (pin "2") (pinfunction "2_2") (pintype "passive"))
      (node (ref "C8") (pin "2") (pinfunction "2_2") (pintype "passive"))
      (node (ref "C9") (pin "2") (pinfunction "2_2") (pintype "passive"))
      (node (ref "CR1") (pin "2") (pinfunction "-_2") (pintype "passive"))
      (node (ref "JDC") (pin "2") (pinfunction "TN_2") (pintype "passive"))
      (node (ref "JP1") (pin "4") (pinfunction "4_4") (pintype "passive"))
      (node (ref "JP2") (pin "2") (pinfunction "2_2") (pintype "passive"))
      (node (ref "JP4") (pin "3") (pinfunction "3_3") (pintype "passive"))
      (node (ref "KF1") (pin "10") (pintype "input"))
      (node (ref "LED") (pin "2") (pinfunction "K_2") (pintype "passive"))
      (node (ref "LED1") (pin "2") (pinfunction "K_2") (pintype "passive"))
      (node (ref "LED2") (pin "2") (pinfunction "K_2") (pintype "passive"))
      (node (ref "LED3") (pin "2") (pinfunction "K_2") (pintype "passive"))
      (node (ref "LED4") (pin "2") (pinfunction "K_2") (pintype "passive"))
      (node (ref "LED5") (pin "2") (pinfunction "K_2") (pintype "passive"))
      (node (ref "LED6") (pin "2") (pinfunction "K_2") (pintype "passive"))
      (node (ref "MIC1") (pin "3") (pinfunction "GND_3") (pintype "passive"))
      (node (ref "MIC2") (pin "3") (pinfunction "GND_3") (pintype "passive"))
      (node (ref "NRF52832") (pin "0") (pinfunction "GND_0") (pintype "passive"))
      (node (ref "NRF52832") (pin "1") (pinfunction "GND_1") (pintype "passive"))
      (node (ref "NRF52832") (pin "15") (pinfunction "GND_15") (pintype "passive"))
      (node (ref "NRF52832") (pin "2") (pinfunction "GND_2") (pintype "passive"))
      (node (ref "NRF52832") (pin "42") (pinfunction "GND_42") (pintype "passive"))
      (node (ref "NRF52832") (pin "43") (pinfunction "GND_43") (pintype "passive"))
      (node (ref "P2") (pin "1") (pinfunction "1_1") (pintype "passive"))
      (node (ref "Q1") (pin "1") (pinfunction "E_1") (pintype "passive"))
      (node (ref "Q2") (pin "1") (pinfunction "E_1") (pintype "passive"))
      (node (ref "Q3") (pin "1") (pinfunction "E_1") (pintype "passive"))
      (node (ref "Q4") (pin "1") (pinfunction "E_1") (pintype "passive"))
      (node (ref "Q5") (pin "1") (pinfunction "E_1") (pintype "passive"))
      (node (ref "R14") (pin "1") (pinfunction "1_1") (pintype "passive"))
      (node (ref "R15") (pin "1") (pinfunction "1_1") (pintype "passive"))
      (node (ref "SW1") (pin "3") (pintype "passive"))
      (node (ref "SW2") (pin "3") (pinfunction "3_3") (pintype "passive"))
      (node (ref "SW3") (pin "3") (pintype "passive"))
      (node (ref "SW5") (pin "3") (pintype "passive"))
      (node (ref "SW6") (pin "3") (pintype "passive"))
    )
    (net (code "60") (name "Net-(C1-Pad1)") (class "Default")
      (node (ref "C1") (pin "1") (pinfunction "1_1") (pintype "passive"))
      (node (ref "R9") (pin "2") (pinfunction "2_2") (pintype "passive"))
    )
    (net (code "61") (name "Net-(C4-Pad1)") (class "Default")
      (node (ref "C4") (pin "1") (pinfunction "1_1") (pintype "passive"))
      (node (ref "R3") (pin "2") (pinfunction "2_2") (pintype "passive"))
    )
    (net (code "62") (name "Net-(C13-Pad1)") (class "Default")
      (node (ref "C13") (pin "1") (pinfunction "1_1") (pintype "passive"))
      (node (ref "R18") (pin "2") (pinfunction "2_2") (pintype "passive"))
    )
    (net (code "63") (name "Net-(C14-Pad1)") (class "Default")
      (node (ref "C14") (pin "1") (pinfunction "1_1") (pintype "passive"))
      (node (ref "R19") (pin "2") (pinfunction "2_2") (pintype "passive"))
    )
    (net (code "64") (name "Net-(CR1-+)") (class "Default")
      (node (ref "C15") (pin "1") (pinfunction "1_1") (pintype "passive"))
      (node (ref "CR1") (pin "1") (pinfunction "+_1") (pintype "passive"))
      (node (ref "SW8") (pin "1") (pinfunction "COM_1") (pintype "passive"))
    )
    (net (code "65") (name "Net-(D1-K)") (class "Default")
      (node (ref "D1") (pin "2") (pinfunction "K_2") (pintype "passive"))
      (node (ref "SW4") (pin "2") (pinfunction "2_2") (pintype "passive"))
    )
    (net (code "66") (name "Net-(D2-A)") (class "Default")
      (node (ref "D2") (pin "1") (pinfunction "A_1") (pintype "passive"))
      (node (ref "Q1") (pin "2") (pinfunction "C_2") (pintype "passive"))
      (node (ref "SP1") (pin "2") (pinfunction "2_2") (pintype "passive"))
    )
    (net (code "67") (name "Net-(D3-A)") (class "Default")
      (node (ref "D3") (pin "1") (pinfunction "A_1") (pintype "passive"))
      (node (ref "Q2") (pin "2") (pinfunction "C_2") (pintype "passive"))
      (node (ref "R23") (pin "1") (pinfunction "1_1") (pintype "passive"))
      (node (ref "RL") (pin "2") (pintype "input"))
    )
    (net (code "68") (name "Net-(D4-A)") (class "Default")
      (node (ref "D4") (pin "1") (pinfunction "A_1") (pintype "passive"))
      (node (ref "Q3") (pin "2") (pinfunction "C_2") (pintype "passive"))
      (node (ref "R24") (pin "1") (pinfunction "1_1") (pintype "passive"))
      (node (ref "RL1") (pin "2") (pintype "input"))
    )
    (net (code "69") (name "Net-(D5-A)") (class "Default")
      (node (ref "D5") (pin "1") (pinfunction "A_1") (pintype "passive"))
      (node (ref "Q4") (pin "2") (pinfunction "C_2") (pintype "passive"))
      (node (ref "R28") (pin "1") (pinfunction "1_1") (pintype "passive"))
      (node (ref "RL2") (pin "2") (pintype "input"))
    )
    (net (code "70") (name "Net-(D6-A)") (class "Default")
      (node (ref "D6") (pin "1") (pinfunction "A_1") (pintype "passive"))
      (node (ref "Q5") (pin "2") (pinfunction "C_2") (pintype "passive"))
      (node (ref "R29") (pin "1") (pinfunction "1_1") (pintype "passive"))
      (node (ref "RL3") (pin "2") (pintype "input"))
    )
    (net (code "71") (name "Net-(LED-A)") (class "Default")
      (node (ref "LED") (pin "1") (pinfunction "A_1") (pintype "passive"))
      (node (ref "R5") (pin "2") (pinfunction "2_2") (pintype "passive"))
    )
    (net (code "72") (name "Net-(LED1-A)") (class "Default")
      (node (ref "LED1") (pin "1") (pinfunction "A_1") (pintype "passive"))
      (node (ref "R6") (pin "2") (pinfunction "2_2") (pintype "passive"))
    )
    (net (code "73") (name "Net-(LED2-A)") (class "Default")
      (node (ref "LED2") (pin "1") (pinfunction "A_1") (pintype "passive"))
      (node (ref "R7") (pin "2") (pinfunction "2_2") (pintype "passive"))
    )
    (net (code "74") (name "Net-(LED3-A)") (class "Default")
      (node (ref "LED3") (pin "1") (pinfunction "A_1") (pintype "passive"))
      (node (ref "R13") (pin "1") (pinfunction "1_1") (pintype "passive"))
    )
    (net (code "75") (name "Net-(LED4-A)") (class "Default")
      (node (ref "LED4") (pin "1") (pinfunction "A_1") (pintype "passive"))
      (node (ref "R20") (pin "2") (pinfunction "2_2") (pintype "passive"))
    )
    (net (code "76") (name "Net-(LED5-A)") (class "Default")
      (node (ref "LED5") (pin "1") (pinfunction "A_1") (pintype "passive"))
      (node (ref "R21") (pin "2") (pinfunction "2_2") (pintype "passive"))
    )
    (net (code "77") (name "Net-(LED6-A)") (class "Default")
      (node (ref "LED6") (pin "1") (pinfunction "A_1") (pintype "passive"))
      (node (ref "R22") (pin "2") (pinfunction "2_2") (pintype "passive"))
    )
    (net (code "78") (name "Net-(LED7-K)") (class "Default")
      (node (ref "LED7") (pin "2") (pinfunction "K_2") (pintype "passive"))
      (node (ref "R23") (pin "2") (pinfunction "2_2") (pintype "passive"))
    )
    (net (code "79") (name "Net-(LED8-K)") (class "Default")
      (node (ref "LED8") (pin "2") (pinfunction "K_2") (pintype "passive"))
      (node (ref "R24") (pin "2") (pinfunction "2_2") (pintype "passive"))
    )
    (net (code "80") (name "Net-(LED9-K)") (class "Default")
      (node (ref "LED9") (pin "2") (pinfunction "K_2") (pintype "passive"))
      (node (ref "R28") (pin "2") (pinfunction "2_2") (pintype "passive"))
    )
    (net (code "81") (name "Net-(LED10-K)") (class "Default")
      (node (ref "LED10") (pin "2") (pinfunction "K_2") (pintype "passive"))
      (node (ref "R29") (pin "2") (pinfunction "2_2") (pintype "passive"))
    )
    (net (code "82") (name "Net-(MIC1-FB)") (class "Default")
      (node (ref "MIC1") (pin "5") (pinfunction "FB_5") (pintype "passive"))
      (node (ref "R11") (pin "1") (pinfunction "1_1") (pintype "passive"))
      (node (ref "R14") (pin "2") (pinfunction "2_2") (pintype "passive"))
    )
    (net (code "83") (name "Net-(MIC1-ON{slash}OFF)") (class "Default")
      (node (ref "C11") (pin "1") (pinfunction "1_1") (pintype "passive"))
      (node (ref "C12") (pin "1") (pinfunction "1_1") (pintype "passive"))
      (node (ref "MIC1") (pin "1") (pinfunction "ON/OFF_1") (pintype "passive"))
      (node (ref "MIC1") (pin "2") (pinfunction "VIN_2") (pintype "passive"))
      (node (ref "SW4") (pin "3") (pinfunction "3_3") (pintype "passive"))
    )
    (net (code "84") (name "Net-(MIC2-FB)") (class "Default")
      (node (ref "MIC2") (pin "5") (pinfunction "FB_5") (pintype "passive"))
      (node (ref "R12") (pin "1") (pinfunction "1_1") (pintype "passive"))
      (node (ref "R15") (pin "2") (pinfunction "2_2") (pintype "passive"))
    )
    (net (code "85") (name "Net-(NRF52832B-P0.21{slash}nRESET)") (class "Default")
      (node (ref "NRF52832") (pin "36") (pinfunction "P0.21/nRESET_36") (pintype "passive"))
      (node (ref "R10") (pin "1") (pinfunction "1_1") (pintype "passive"))
    )
    (net (code "86") (name "Net-(Q1-B)") (class "Default")
      (node (ref "Q1") (pin "3") (pinfunction "B_3") (pintype "passive"))
      (node (ref "R25") (pin "1") (pinfunction "1_1") (pintype "passive"))
    )
    (net (code "87") (name "Net-(Q2-B)") (class "Default")
      (node (ref "Q2") (pin "3") (pinfunction "B_3") (pintype "passive"))
      (node (ref "R26") (pin "1") (pinfunction "1_1") (pintype "passive"))
    )
    (net (code "88") (name "Net-(Q3-B)") (class "Default")
      (node (ref "Q3") (pin "3") (pinfunction "B_3") (pintype "passive"))
      (node (ref "R27") (pin "1") (pinfunction "1_1") (pintype "passive"))
    )
    (net (code "89") (name "Net-(Q4-B)") (class "Default")
      (node (ref "Q4") (pin "3") (pinfunction "B_3") (pintype "passive"))
      (node (ref "R30") (pin "1") (pinfunction "1_1") (pintype "passive"))
    )
    (net (code "90") (name "Net-(Q5-B)") (class "Default")
      (node (ref "Q5") (pin "3") (pinfunction "B_3") (pintype "passive"))
      (node (ref "R31") (pin "1") (pinfunction "1_1") (pintype "passive"))
    )
    (net (code "91") (name "Net-(R4-Pad1)") (class "Default")
      (node (ref "R4") (pin "1") (pinfunction "1_1") (pintype "passive"))
      (node (ref "SW2") (pin "1") (pinfunction "1_1") (pintype "passive"))
    )
    (net (code "92") (name "unconnected-(A-IO2-Pad24)") (class "Default")
      (node (ref "A") (pin "24") (pinfunction "IO2_24") (pintype "bidirectional+no_connect"))
    )
    (net (code "93") (name "unconnected-(A-IO12-Pad14)") (class "Default")
      (node (ref "A") (pin "14") (pinfunction "IO12_14") (pintype "bidirectional+no_connect"))
    )
    (net (code "94") (name "unconnected-(A-IO34-Pad6)") (class "Default")
      (node (ref "A") (pin "6") (pinfunction "IO34_6") (pintype "input+no_connect"))
    )
    (net (code "95") (name "unconnected-(A-IO35-Pad7)") (class "Default")
      (node (ref "A") (pin "7") (pinfunction "IO35_7") (pintype "input+no_connect"))
    )
    (net (code "96") (name "unconnected-(A-SCK{slash}CLK-Pad20)") (class "Default")
      (node (ref "A") (pin "20") (pinfunction "SCK/CLK_20") (pintype "bidirectional+no_connect"))
    )
    (net (code "97") (name "unconnected-(A-SCS{slash}CMD-Pad19)") (class "Default")
      (node (ref "A") (pin "19") (pinfunction "SCS/CMD_19") (pintype "bidirectional+no_connect"))
    )
    (net (code "98") (name "unconnected-(A-SDI{slash}SD1-Pad22)") (class "Default")
      (node (ref "A") (pin "22") (pinfunction "SDI/SD1_22") (pintype "bidirectional+no_connect"))
    )
    (net (code "99") (name "unconnected-(A-SDO{slash}SD0-Pad21)") (class "Default")
      (node (ref "A") (pin "21") (pinfunction "SDO/SD0_21") (pintype "bidirectional+no_connect"))
    )
    (net (code "100") (name "unconnected-(A-SENSOR_VN-Pad5)") (class "Default")
      (node (ref "A") (pin "5") (pinfunction "SENSOR_VN_5") (pintype "input+no_connect"))
    )
    (net (code "101") (name "unconnected-(A-SENSOR_VP-Pad4)") (class "Default")
      (node (ref "A") (pin "4") (pinfunction "SENSOR_VP_4") (pintype "input+no_connect"))
    )
    (net (code "102") (name "unconnected-(A-SHD{slash}SD2-Pad17)") (class "Default")
      (node (ref "A") (pin "17") (pinfunction "SHD/SD2_17") (pintype "bidirectional+no_connect"))
    )
    (net (code "103") (name "unconnected-(A-SWP{slash}SD3-Pad18)") (class "Default")
      (node (ref "A") (pin "18") (pinfunction "SWP/SD3_18") (pintype "bidirectional+no_connect"))
    )
    (net (code "104") (name "unconnected-(JDC-S-Pad3)") (class "Default")
      (node (ref "JDC") (pin "3") (pinfunction "S_3") (pintype "power_in+no_connect"))
    )
    (net (code "105") (name "unconnected-(NRF52832B-DCC-Pad13)") (class "Default")
      (node (ref "NRF52832") (pin "13") (pinfunction "DCC_13") (pintype "passive+no_connect"))
    )
    (net (code "106") (name "unconnected-(NRF52832B-DEC1-Pad14)") (class "Default")
      (node (ref "NRF52832") (pin "14") (pinfunction "DEC1_14") (pintype "passive+no_connect"))
    )
    (net (code "107") (name "unconnected-(NRF52832B-DEC2-Pad3)") (class "Default")
      (node (ref "NRF52832") (pin "3") (pinfunction "DEC2_3") (pintype "passive+no_connect"))
    )
    (net (code "108") (name "unconnected-(NRF52832B-DEC3-Pad4)") (class "Default")
      (node (ref "NRF52832") (pin "4") (pinfunction "DEC3_4") (pintype "passive+no_connect"))
    )
    (net (code "109") (name "unconnected-(NRF52832B-DEC4-Pad12)") (class "Default")
      (node (ref "NRF52832") (pin "12") (pinfunction "DEC4_12") (pintype "passive+no_connect"))
    )
    (net (code "110") (name "unconnected-(NRF52832B-P0.16-Pad31)") (class "Default")
      (node (ref "NRF52832") (pin "31") (pinfunction "P0.16_31") (pintype "passive+no_connect"))
    )
    (net (code "111") (name "unconnected-(NRF52832B-P0.19-Pad34)") (class "Default")
      (node (ref "NRF52832") (pin "34") (pinfunction "P0.19_34") (pintype "passive+no_connect"))
    )
    (net (code "112") (name "unconnected-(NRF52832B-P0.20-Pad35)") (class "Default")
      (node (ref "NRF52832") (pin "35") (pinfunction "P0.20_35") (pintype "passive+no_connect"))
    )
    (net (code "113") (name "unconnected-(NRF52832B-P0.22-Pad39)") (class "Default")
      (node (ref "NRF52832") (pin "39") (pinfunction "P0.22_39") (pintype "passive+no_connect"))
    )
    (net (code "114") (name "unconnected-(NRF52832B-P0.23-Pad40)") (class "Default")
      (node (ref "NRF52832") (pin "40") (pinfunction "P0.23_40") (pintype "passive+no_connect"))
    )
    (net (code "115") (name "unconnected-(SW1-Pad1)") (class "Default")
      (node (ref "SW1") (pin "1") (pintype "passive+no_connect"))
    )
    (net (code "116") (name "unconnected-(SW1-Pad2)") (class "Default")
      (node (ref "SW1") (pin "2") (pintype "passive+no_connect"))
    )
    (net (code "117") (name "unconnected-(SW3-Pad1)") (class "Default")
      (node (ref "SW3") (pin "1") (pintype "passive+no_connect"))
    )
    (net (code "118") (name "unconnected-(SW3-Pad2)") (class "Default")
      (node (ref "SW3") (pin "2") (pintype "passive+no_connect"))
    )
    (net (code "119") (name "unconnected-(SW4-Pad1)") (class "Default")
      (node (ref "SW4") (pin "1") (pinfunction "1_1") (pintype "passive+no_connect"))
    )
    (net (code "120") (name "unconnected-(SW5-Pad1)") (class "Default")
      (node (ref "SW5") (pin "1") (pintype "passive+no_connect"))
    )
    (net (code "121") (name "unconnected-(SW5-Pad2)") (class "Default")
      (node (ref "SW5") (pin "2") (pintype "passive+no_connect"))
    )
    (net (code "122") (name "unconnected-(SW6-Pad1)") (class "Default")
      (node (ref "SW6") (pin "1") (pintype "passive+no_connect"))
    )
    (net (code "123") (name "unconnected-(SW6-Pad2)") (class "Default")
      (node (ref "SW6") (pin "2") (pintype "passive+no_connect"))
    )
    (net (code "124") (name "unconnected-(SW7-NO-Pad3)") (class "Default")
      (node (ref "SW7") (pin "3") (pinfunction "NO_3") (pintype "passive+no_connect"))
    )
    (net (code "125") (name "unconnected-(SW8-NO-Pad3)") (class "Default")
      (node (ref "SW8") (pin "3") (pinfunction "NO_3") (pintype "passive+no_connect"))
    )
    (net (code "126") (name "unconnected-(SW9-NO-Pad3)") (class "Default")
      (node (ref "SW9") (pin "3") (pinfunction "NO_3") (pintype "passive+no_connect"))
    )
    (net (code "127") (name "unconnected-(VIT1-1-PadVIT1)") (class "Default")
      (node (ref "VIT1") (pin "VIT1") (pinfunction "1_VIT1") (pintype "passive"))
    )
    (net (code "128") (name "unconnected-(VIT2-1-PadVIT1)") (class "Default")
      (node (ref "VIT2") (pin "VIT1") (pinfunction "1_VIT1") (pintype "passive"))
    )
    (net (code "129") (name "unconnected-(VIT3-1-PadVIT1)") (class "Default")
      (node (ref "VIT3") (pin "VIT1") (pinfunction "1_VIT1") (pintype "passive"))
    )
    (net (code "130") (name "unconnected-(VIT4-1-PadVIT1)") (class "Default")
      (node (ref "VIT4") (pin "VIT1") (pinfunction "1_VIT1") (pintype "passive"))
    )
  )
)
